# MICROSD_CARD.net
KiCad netlist of a schematic drawn in Altium Designer
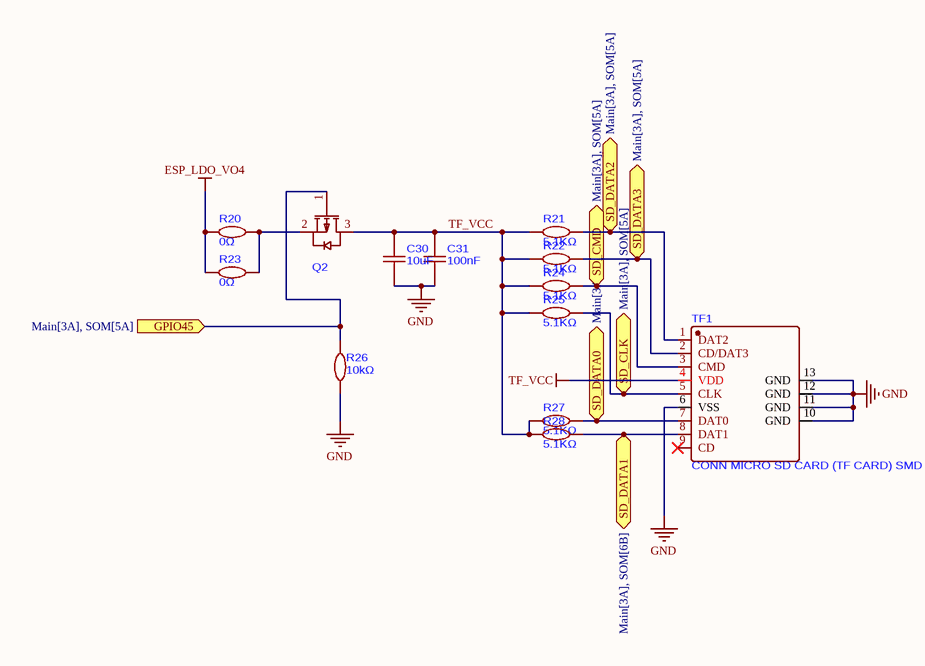
[diagram p0: MICROSD CARD.SchDoc]

(export (version "E")
  (design (tool "Eeschema 10.0.6"))
  (components
    (comp (ref "C30")
      (value "10uF")
      (footprint "C0603")
      (description "25V 10uF X5R ±20% 0603 Ceramic Capacitors ROHS")
      (libsource (lib "Schlib2") (part "CL10A106MA8NRNC"))
    )
    (comp (ref "C31")
      (value "100nF")
      (footprint "C0603")
      (description "50V 100nF X7R ±10% 0603 Ceramic Capacitors ROHS")
      (libsource (lib "Schlib2") (part "CC0603KRX7R9BB104"))
    )
    (comp (ref "Q2")
      (value "MOSFET P-CH 30V 4.3A SOT-23")
      (footprint "SOT-23-3_L2.9-W1.6-P1.90-LS2.8-BR")
      (description "30V 4.3A 48mΩ@10V 2.5V@250uA 1 P-Channel SOT-23 Single FETs, MOSFETs ROHS")
      (libsource (lib "Schlib2") (part "AO3407A"))
    )
    (comp (ref "R20")
      (value "0Ω")
      (footprint "R0603")
      (description "100mW 0Ω 75V Thick Film Resistor ±5% 0603 Chip Resistor - Surface Mount RoHS")
      (libsource (lib "Schlib2") (part "RC0603JR-070RL"))
    )
    (comp (ref "R21")
      (value "5.1KΩ")
      (footprint "R0603")
      (description "100mW 5.1kΩ 75V ±100ppm/℃ Thick Film Resistor ±1% 0603 Chip Resistor - Surface Mount RoHS")
      (libsource (lib "Schlib2") (part "FRC0603F5101TS"))
    )
    (comp (ref "R22")
      (value "5.1KΩ")
      (footprint "R0603")
      (description "100mW 5.1kΩ 75V ±100ppm/℃ Thick Film Resistor ±1% 0603 Chip Resistor - Surface Mount RoHS")
      (libsource (lib "Schlib2") (part "FRC0603F5101TS"))
    )
    (comp (ref "R23")
      (value "0Ω")
      (footprint "R0603")
      (description "100mW 0Ω 75V Thick Film Resistor ±5% 0603 Chip Resistor - Surface Mount RoHS")
      (libsource (lib "Schlib2") (part "RC0603JR-070RL"))
    )
    (comp (ref "R24")
      (value "5.1KΩ")
      (footprint "R0603")
      (description "100mW 5.1kΩ 75V ±100ppm/℃ Thick Film Resistor ±1% 0603 Chip Resistor - Surface Mount RoHS")
      (libsource (lib "Schlib2") (part "FRC0603F5101TS"))
    )
    (comp (ref "R25")
      (value "5.1KΩ")
      (footprint "R0603")
      (description "100mW 5.1kΩ 75V ±100ppm/℃ Thick Film Resistor ±1% 0603 Chip Resistor - Surface Mount RoHS")
      (libsource (lib "Schlib2") (part "FRC0603F5101TS"))
    )
    (comp (ref "R26")
      (value "10kΩ")
      (footprint "R0603")
      (description "100mW 10kΩ 75V ±100ppm/℃ Thick Film Resistor ±1% 0603 Chip Resistor - Surface Mount ROHS")
      (libsource (lib "Schlib2") (part "RC0603FR-0710KL"))
    )
    (comp (ref "R27")
      (value "5.1KΩ")
      (footprint "R0603")
      (description "100mW 5.1kΩ 75V ±100ppm/℃ Thick Film Resistor ±1% 0603 Chip Resistor - Surface Mount RoHS")
      (libsource (lib "Schlib2") (part "FRC0603F5101TS"))
    )
    (comp (ref "R28")
      (value "5.1KΩ")
      (footprint "R0603")
      (description "100mW 5.1kΩ 75V ±100ppm/℃ Thick Film Resistor ±1% 0603 Chip Resistor - Surface Mount RoHS")
      (libsource (lib "Schlib2") (part "FRC0603F5101TS"))
    )
    (comp (ref "TF1")
      (value "CONN MICRO SD CARD (TF CARD) SMD")
      (footprint "TF-SMD_SH_SH-TF-01B")
      (description "-25℃~+85℃ Push-Push 2mm Connector and Ejector MicroSD Card (TF Card) SMD PC Card Sockets RoHS")
      (libsource (lib "Schlib2") (part "SH-TF-01A"))
    )
  )
  (nets
    (net (code "1") (name "/GPIO45") (class "Default")
      (node (ref "Q2") (pin "1") (pinfunction "G_1") (pintype "passive"))
      (node (ref "R26") (pin "2") (pinfunction "2_2") (pintype "passive"))
    )
    (net (code "2") (name "/SD_CLK") (class "Default")
      (node (ref "R25") (pin "2") (pinfunction "2_2") (pintype "passive"))
      (node (ref "TF1") (pin "5") (pinfunction "CLK_5") (pintype "passive"))
    )
    (net (code "3") (name "/SD_CMD") (class "Default")
      (node (ref "R24") (pin "2") (pinfunction "2_2") (pintype "passive"))
      (node (ref "TF1") (pin "3") (pinfunction "CMD_3") (pintype "passive"))
    )
    (net (code "4") (name "/SD_DATA0") (class "Default")
      (node (ref "R27") (pin "2") (pinfunction "2_2") (pintype "passive"))
      (node (ref "TF1") (pin "7") (pinfunction "DAT0_7") (pintype "passive"))
    )
    (net (code "5") (name "/SD_DATA1") (class "Default")
      (node (ref "R28") (pin "2") (pinfunction "2_2") (pintype "passive"))
      (node (ref "TF1") (pin "8") (pinfunction "DAT1_8") (pintype "passive"))
    )
    (net (code "6") (name "/SD_DATA2") (class "Default")
      (node (ref "R21") (pin "2") (pinfunction "2_2") (pintype "passive"))
      (node (ref "TF1") (pin "1") (pinfunction "DAT2_1") (pintype "passive"))
    )
    (net (code "7") (name "/SD_DATA3") (class "Default")
      (node (ref "R22") (pin "2") (pinfunction "2_2") (pintype "passive"))
      (node (ref "TF1") (pin "2") (pinfunction "CD/DAT3_2") (pintype "passive"))
    )
    (net (code "8") (name "ESP_LDO_VO4") (class "Default")
      (node (ref "R20") (pin "1") (pinfunction "1_1") (pintype "passive"))
      (node (ref "R23") (pin "1") (pinfunction "1_1") (pintype "passive"))
    )
    (net (code "9") (name "GND") (class "Default")
      (node (ref "C30") (pin "1") (pinfunction "1_1") (pintype "passive"))
      (node (ref "C31") (pin "1") (pinfunction "1_1") (pintype "passive"))
      (node (ref "R26") (pin "1") (pinfunction "1_1") (pintype "passive"))
      (node (ref "TF1") (pin "10") (pinfunction "GND_10") (pintype "passive"))
      (node (ref "TF1") (pin "11") (pinfunction "GND_11") (pintype "passive"))
      (node (ref "TF1") (pin "12") (pinfunction "GND_12") (pintype "passive"))
      (node (ref "TF1") (pin "13") (pinfunction "GND_13") (pintype "passive"))
      (node (ref "TF1") (pin "6") (pinfunction "VSS_6") (pintype "passive"))
    )
    (net (code "10") (name "Net-(Q2-S)") (class "Default")
      (node (ref "Q2") (pin "2") (pinfunction "S_2") (pintype "passive"))
      (node (ref "R20") (pin "2") (pinfunction "2_2") (pintype "passive"))
      (node (ref "R23") (pin "2") (pinfunction "2_2") (pintype "passive"))
    )
    (net (code "11") (name "TF_VCC") (class "Default")
      (node (ref "C30") (pin "2") (pinfunction "2_2") (pintype "passive"))
      (node (ref "C31") (pin "2") (pinfunction "2_2") (pintype "passive"))
      (node (ref "Q2") (pin "3") (pinfunction "D_3") (pintype "passive"))
      (node (ref "R21") (pin "1") (pinfunction "1_1") (pintype "passive"))
      (node (ref "R22") (pin "1") (pinfunction "1_1") (pintype "passive"))
      (node (ref "R24") (pin "1") (pinfunction "1_1") (pintype "passive"))
      (node (ref "R25") (pin "1") (pinfunction "1_1") (pintype "passive"))
      (node (ref "R27") (pin "1") (pinfunction "1_1") (pintype "passive"))
      (node (ref "R28") (pin "1") (pinfunction "1_1") (pintype "passive"))
      (node (ref "TF1") (pin "4") (pinfunction "VDD_4") (pintype "passive"))
    )
    (net (code "12") (name "unconnected-(TF1-CD-Pad9)") (class "Default")
      (node (ref "TF1") (pin "9") (pinfunction "CD_9") (pintype "passive+no_connect"))
    )
  )
)
